# amr-breakout.net
KiCad netlist of a schematic drawn in EAGLE
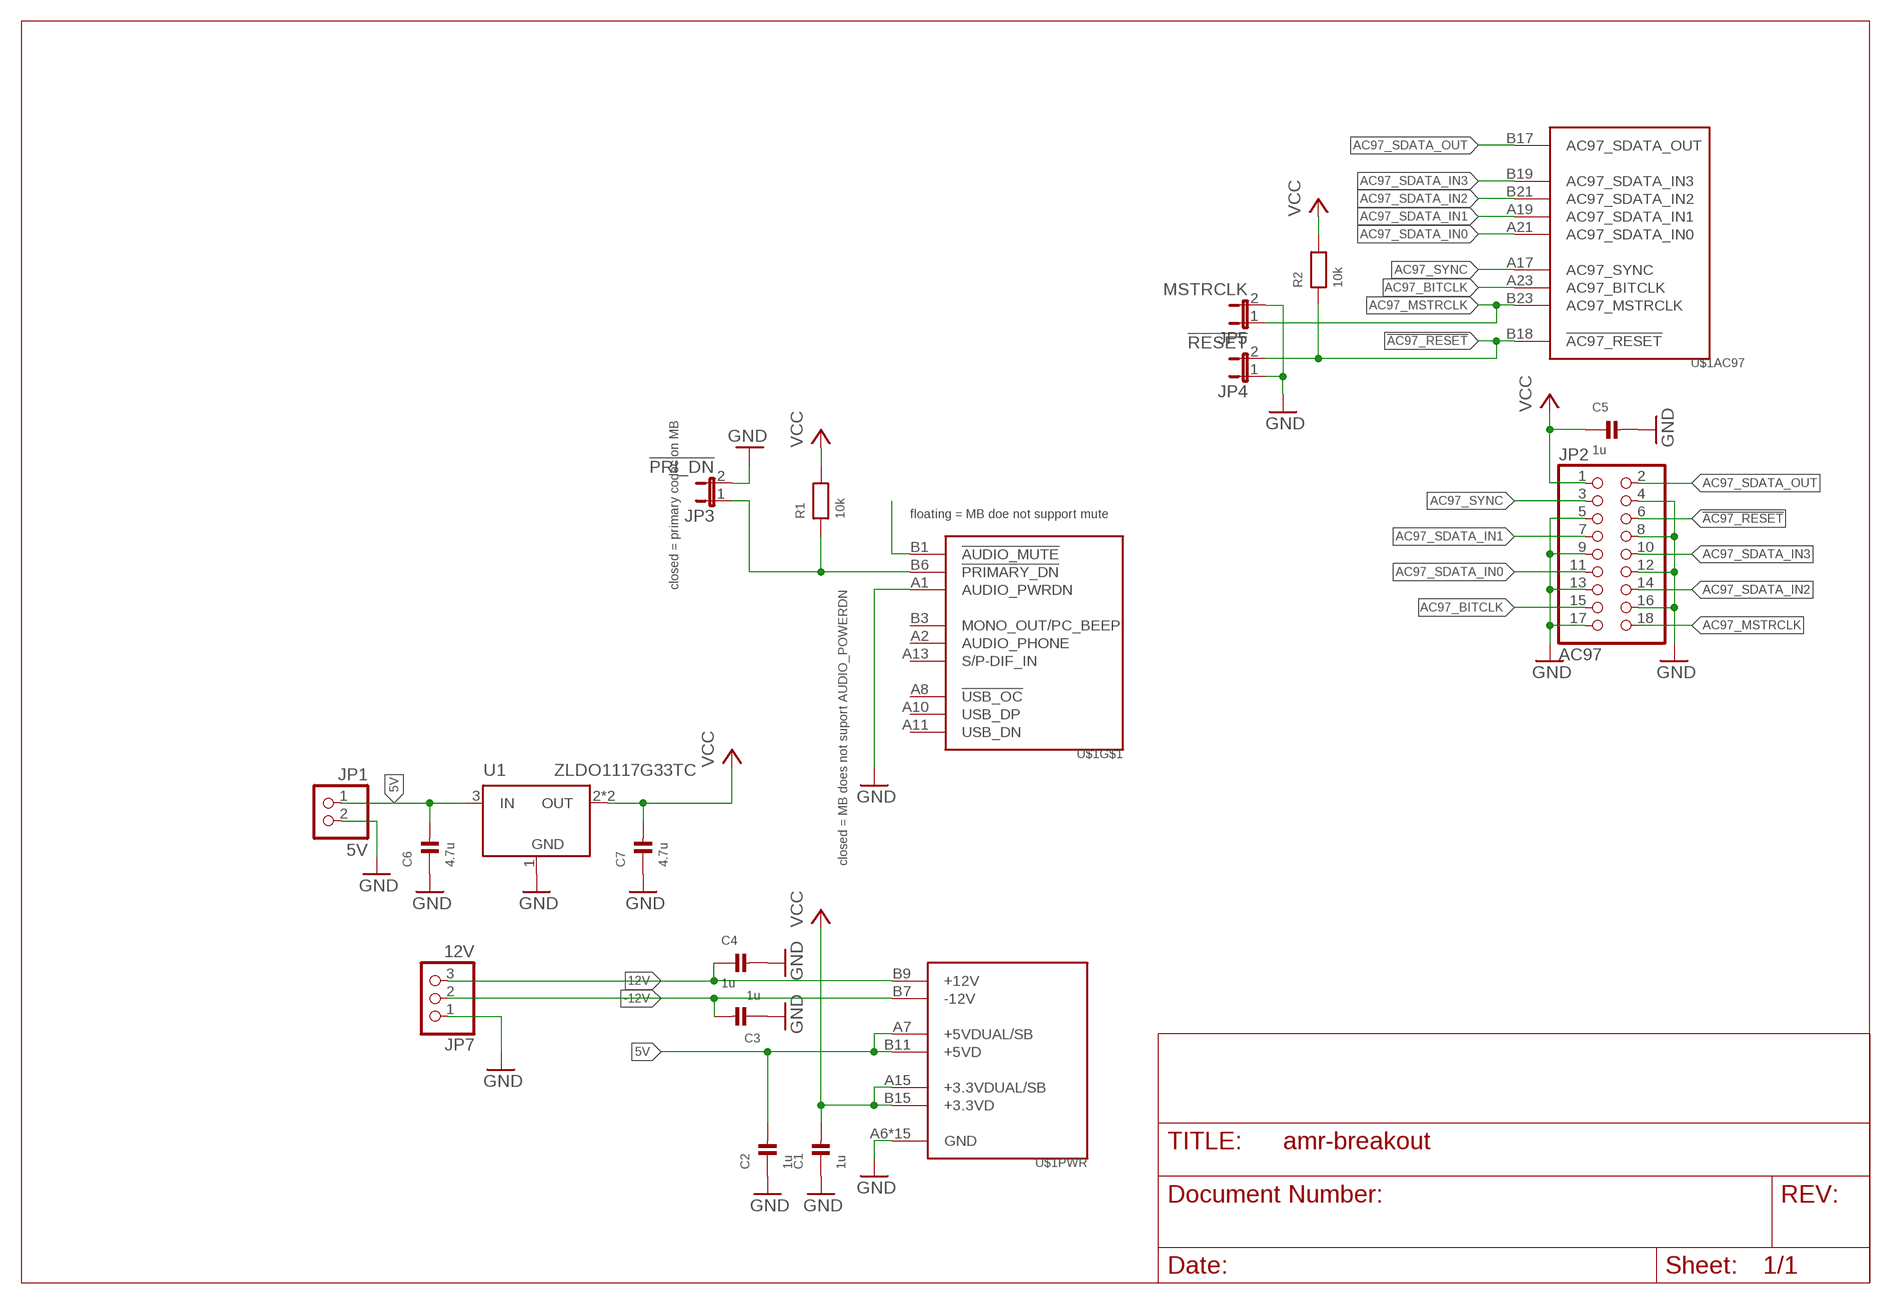
[diagram p0: schematic, sheet 1]

(export (version "E")
  (design (tool "Eeschema 10.0.6"))
  (components
    (comp (ref "C1")
      (value "1u")
      (footprint "eagle-import:_0603")
      (libsource (lib "eagle-import") (part "CAP_CERAMIC_0603"))
    )
    (comp (ref "C2")
      (value "1u")
      (footprint "eagle-import:_0603")
      (libsource (lib "eagle-import") (part "CAP_CERAMIC_0603"))
    )
    (comp (ref "C3")
      (value "1u")
      (footprint "eagle-import:_0603")
      (libsource (lib "eagle-import") (part "CAP_CERAMIC_0603"))
    )
    (comp (ref "C4")
      (value "1u")
      (footprint "eagle-import:_0603")
      (libsource (lib "eagle-import") (part "CAP_CERAMIC_0603"))
    )
    (comp (ref "C5")
      (value "1u")
      (footprint "eagle-import:_0603")
      (libsource (lib "eagle-import") (part "CAP_CERAMIC_0603"))
    )
    (comp (ref "C6")
      (value "4.7u")
      (footprint "eagle-import:_0805")
      (libsource (lib "eagle-import") (part "CAP_CERAMIC_0805"))
    )
    (comp (ref "C7")
      (value "4.7u")
      (footprint "eagle-import:_0805")
      (libsource (lib "eagle-import") (part "CAP_CERAMIC_0805"))
    )
    (comp (ref "JP1")
      (value "5V")
      (footprint "eagle-import:1X02")
      (libsource (lib "eagle-import") (part "PINHD-1X2"))
    )
    (comp (ref "JP2")
      (value "AC97")
      (footprint "eagle-import:2X09")
      (libsource (lib "eagle-import") (part "PINHD-2X9"))
    )
    (comp (ref "JP3")
      (value "!PRI_DN")
      (footprint "eagle-import:JP1")
      (libsource (lib "eagle-import") (part "JP1E"))
    )
    (comp (ref "JP4")
      (value "!RESET")
      (footprint "eagle-import:JP1")
      (libsource (lib "eagle-import") (part "JP1E"))
    )
    (comp (ref "JP5")
      (value "MSTRCLK")
      (footprint "eagle-import:JP1")
      (libsource (lib "eagle-import") (part "JP1E"))
    )
    (comp (ref "JP7")
      (value "12V")
      (footprint "eagle-import:1X03")
      (libsource (lib "eagle-import") (part "PINHD-1X3"))
    )
    (comp (ref "R1")
      (value "10k")
      (footprint "eagle-import:_0603")
      (libsource (lib "eagle-import") (part "RESISTOR_0603"))
    )
    (comp (ref "R2")
      (value "10k")
      (footprint "eagle-import:_0603")
      (libsource (lib "eagle-import") (part "RESISTOR_0603"))
    )
    (comp (ref "U$1")
      (value "AMR-SLOT")
      (footprint "eagle-import:5650090-7")
      (libsource (lib "eagle-import") (part "AMR-SLOT"))
    )
    (comp (ref "U1")
      (value "ZLDO1117G33TC")
      (footprint "eagle-import:SOT223")
      (libsource (lib "eagle-import") (part "LDO-TLV1117"))
    )
  )
  (nets
    (net (code "1") (name "-12V") (class "Default")
      (node (ref "C3") (pin "2") (pinfunction "2_2") (pintype "passive"))
      (node (ref "JP7") (pin "2") (pinfunction "2_2") (pintype "passive"))
      (node (ref "U$1") (pin "B7") (pinfunction "-12V_B7") (pintype "passive"))
    )
    (net (code "2") (name "/~{AC97_RESET}") (class "Default")
      (node (ref "JP2") (pin "6") (pinfunction "6_6") (pintype "passive"))
      (node (ref "JP4") (pin "2") (pinfunction "2_2") (pintype "passive"))
      (node (ref "R2") (pin "1") (pinfunction "1_1") (pintype "passive"))
      (node (ref "U$1") (pin "B18") (pinfunction "~{AC97_RESET}_B18") (pintype "input"))
    )
    (net (code "3") (name "5V") (class "Default")
      (node (ref "C2") (pin "2") (pinfunction "2_2") (pintype "passive"))
      (node (ref "C6") (pin "2") (pinfunction "2_2") (pintype "passive"))
      (node (ref "JP1") (pin "1") (pinfunction "1_1") (pintype "passive"))
      (node (ref "U$1") (pin "A7") (pinfunction "+5VDUAL/SB_A7") (pintype "passive"))
      (node (ref "U$1") (pin "B11") (pinfunction "+5VD_B11") (pintype "passive"))
      (node (ref "U1") (pin "3") (pinfunction "IN_3") (pintype "input"))
    )
    (net (code "4") (name "12V") (class "Default")
      (node (ref "C4") (pin "1") (pinfunction "1_1") (pintype "passive"))
      (node (ref "JP7") (pin "3") (pinfunction "3_3") (pintype "passive"))
      (node (ref "U$1") (pin "B9") (pinfunction "+12V_B9") (pintype "passive"))
    )
    (net (code "5") (name "AC97_BITCLK") (class "Default")
      (node (ref "JP2") (pin "15") (pinfunction "15_15") (pintype "passive"))
      (node (ref "U$1") (pin "A23") (pinfunction "AC97_BITCLK_A23") (pintype "bidirectional"))
    )
    (net (code "6") (name "AC97_MSTRCLK") (class "Default")
      (node (ref "JP2") (pin "18") (pinfunction "18_18") (pintype "passive"))
      (node (ref "JP5") (pin "1") (pinfunction "1_1") (pintype "passive"))
      (node (ref "U$1") (pin "B23") (pinfunction "AC97_MSTRCLK_B23") (pintype "input"))
    )
    (net (code "7") (name "AC97_SDATA_IN0") (class "Default")
      (node (ref "JP2") (pin "11") (pinfunction "11_11") (pintype "passive"))
      (node (ref "U$1") (pin "A21") (pinfunction "AC97_SDATA_IN0_A21") (pintype "output"))
    )
    (net (code "8") (name "AC97_SDATA_IN1") (class "Default")
      (node (ref "JP2") (pin "7") (pinfunction "7_7") (pintype "passive"))
      (node (ref "U$1") (pin "A19") (pinfunction "AC97_SDATA_IN1_A19") (pintype "output"))
    )
    (net (code "9") (name "AC97_SDATA_IN2") (class "Default")
      (node (ref "JP2") (pin "14") (pinfunction "14_14") (pintype "passive"))
      (node (ref "U$1") (pin "B21") (pinfunction "AC97_SDATA_IN2_B21") (pintype "output"))
    )
    (net (code "10") (name "AC97_SDATA_IN3") (class "Default")
      (node (ref "JP2") (pin "10") (pinfunction "10_10") (pintype "passive"))
      (node (ref "U$1") (pin "B19") (pinfunction "AC97_SDATA_IN3_B19") (pintype "output"))
    )
    (net (code "11") (name "AC97_SDATA_OUT") (class "Default")
      (node (ref "JP2") (pin "2") (pinfunction "2_2") (pintype "passive"))
      (node (ref "U$1") (pin "B17") (pinfunction "AC97_SDATA_OUT_B17") (pintype "input"))
    )
    (net (code "12") (name "AC97_SYNC") (class "Default")
      (node (ref "JP2") (pin "3") (pinfunction "3_3") (pintype "passive"))
      (node (ref "U$1") (pin "A17") (pinfunction "AC97_SYNC_A17") (pintype "input"))
    )
    (net (code "13") (name "GND") (class "Default")
      (node (ref "C1") (pin "1") (pinfunction "1_1") (pintype "passive"))
      (node (ref "C2") (pin "1") (pinfunction "1_1") (pintype "passive"))
      (node (ref "C3") (pin "1") (pinfunction "1_1") (pintype "passive"))
      (node (ref "C4") (pin "2") (pinfunction "2_2") (pintype "passive"))
      (node (ref "C5") (pin "2") (pinfunction "2_2") (pintype "passive"))
      (node (ref "C6") (pin "1") (pinfunction "1_1") (pintype "passive"))
      (node (ref "C7") (pin "1") (pinfunction "1_1") (pintype "passive"))
      (node (ref "JP1") (pin "2") (pinfunction "2_2") (pintype "passive"))
      (node (ref "JP2") (pin "12") (pinfunction "12_12") (pintype "passive"))
      (node (ref "JP2") (pin "13") (pinfunction "13_13") (pintype "passive"))
      (node (ref "JP2") (pin "16") (pinfunction "16_16") (pintype "passive"))
      (node (ref "JP2") (pin "17") (pinfunction "17_17") (pintype "passive"))
      (node (ref "JP2") (pin "4") (pinfunction "4_4") (pintype "passive"))
      (node (ref "JP2") (pin "5") (pinfunction "5_5") (pintype "passive"))
      (node (ref "JP2") (pin "8") (pinfunction "8_8") (pintype "passive"))
      (node (ref "JP2") (pin "9") (pinfunction "9_9") (pintype "passive"))
      (node (ref "JP3") (pin "2") (pinfunction "2_2") (pintype "passive"))
      (node (ref "JP4") (pin "1") (pinfunction "1_1") (pintype "passive"))
      (node (ref "JP5") (pin "2") (pinfunction "2_2") (pintype "passive"))
      (node (ref "JP7") (pin "1") (pinfunction "1_1") (pintype "passive"))
      (node (ref "U$1") (pin "A1") (pinfunction "AUDIO_PWRDN_A1") (pintype "input"))
      (node (ref "U$1") (pin "A12") (pinfunction "GND_A12") (pintype "passive"))
      (node (ref "U$1") (pin "A14") (pinfunction "GND_A14") (pintype "passive"))
      (node (ref "U$1") (pin "A16") (pinfunction "GND_A16") (pintype "passive"))
      (node (ref "U$1") (pin "A18") (pinfunction "GND_A18") (pintype "passive"))
      (node (ref "U$1") (pin "A20") (pinfunction "GND_A20") (pintype "passive"))
      (node (ref "U$1") (pin "A22") (pinfunction "GND_A22") (pintype "passive"))
      (node (ref "U$1") (pin "A6") (pinfunction "GND_A6") (pintype "passive"))
      (node (ref "U$1") (pin "A9") (pinfunction "GND_A9") (pintype "passive"))
      (node (ref "U$1") (pin "B10") (pinfunction "GND_B10") (pintype "passive"))
      (node (ref "U$1") (pin "B12") (pinfunction "GND_B12") (pintype "passive"))
      (node (ref "U$1") (pin "B16") (pinfunction "GND_B16") (pintype "passive"))
      (node (ref "U$1") (pin "B2") (pinfunction "GND_B2") (pintype "passive"))
      (node (ref "U$1") (pin "B20") (pinfunction "GND_B20") (pintype "passive"))
      (node (ref "U$1") (pin "B22") (pinfunction "GND_B22") (pintype "passive"))
      (node (ref "U$1") (pin "B8") (pinfunction "GND_B8") (pintype "passive"))
      (node (ref "U1") (pin "1") (pinfunction "GND_1") (pintype "power_in"))
    )
    (net (code "14") (name "Net-(U$1B-~{PRIMARY_DN})") (class "Default")
      (node (ref "JP3") (pin "1") (pinfunction "1_1") (pintype "passive"))
      (node (ref "R1") (pin "1") (pinfunction "1_1") (pintype "passive"))
      (node (ref "U$1") (pin "B6") (pinfunction "~{PRIMARY_DN}_B6") (pintype "input"))
    )
    (net (code "15") (name "VCC") (class "Default")
      (node (ref "C1") (pin "2") (pinfunction "2_2") (pintype "passive"))
      (node (ref "C5") (pin "1") (pinfunction "1_1") (pintype "passive"))
      (node (ref "C7") (pin "2") (pinfunction "2_2") (pintype "passive"))
      (node (ref "JP2") (pin "1") (pinfunction "1_1") (pintype "passive"))
      (node (ref "R1") (pin "2") (pinfunction "2_2") (pintype "passive"))
      (node (ref "R2") (pin "2") (pinfunction "2_2") (pintype "passive"))
      (node (ref "U$1") (pin "A15") (pinfunction "+3.3VDUAL/SB_A15") (pintype "passive"))
      (node (ref "U$1") (pin "B15") (pinfunction "+3.3VD_B15") (pintype "passive"))
      (node (ref "U1") (pin "2") (pinfunction "OUT_2") (pintype "passive"))
      (node (ref "U1") (pin "4") (pinfunction "OUT_4") (pintype "passive"))
    )
    (net (code "16") (name "unconnected-(U$1B-AUDIO_PHONE-PadA2)") (class "Default")
      (node (ref "U$1") (pin "A2") (pinfunction "AUDIO_PHONE_A2") (pintype "passive"))
    )
    (net (code "17") (name "unconnected-(U$1B-MONO_OUT{slash}PC_BEEP-PadB3)") (class "Default")
      (node (ref "U$1") (pin "B3") (pinfunction "MONO_OUT/PC_BEEP_B3") (pintype "passive"))
    )
    (net (code "18") (name "unconnected-(U$1B-S{slash}P-DIF_IN-PadA13)") (class "Default")
      (node (ref "U$1") (pin "A13") (pinfunction "S/P-DIF_IN_A13") (pintype "input"))
    )
    (net (code "19") (name "unconnected-(U$1B-USB_DN-PadA11)") (class "Default")
      (node (ref "U$1") (pin "A11") (pinfunction "USB_DN_A11") (pintype "bidirectional"))
    )
    (net (code "20") (name "unconnected-(U$1B-USB_DP-PadA10)") (class "Default")
      (node (ref "U$1") (pin "A10") (pinfunction "USB_DP_A10") (pintype "bidirectional"))
    )
    (net (code "21") (name "unconnected-(U$1B-~{AUDIO_MUTE}-PadB1)") (class "Default")
      (node (ref "U$1") (pin "B1") (pinfunction "~{AUDIO_MUTE}_B1") (pintype "input"))
    )
    (net (code "22") (name "unconnected-(U$1B-~{USB_OC}-PadA8)") (class "Default")
      (node (ref "U$1") (pin "A8") (pinfunction "~{USB_OC}_A8") (pintype "output"))
    )
  )
)
